# main_esp.net
KiCad netlist of a schematic drawn in Altium Designer
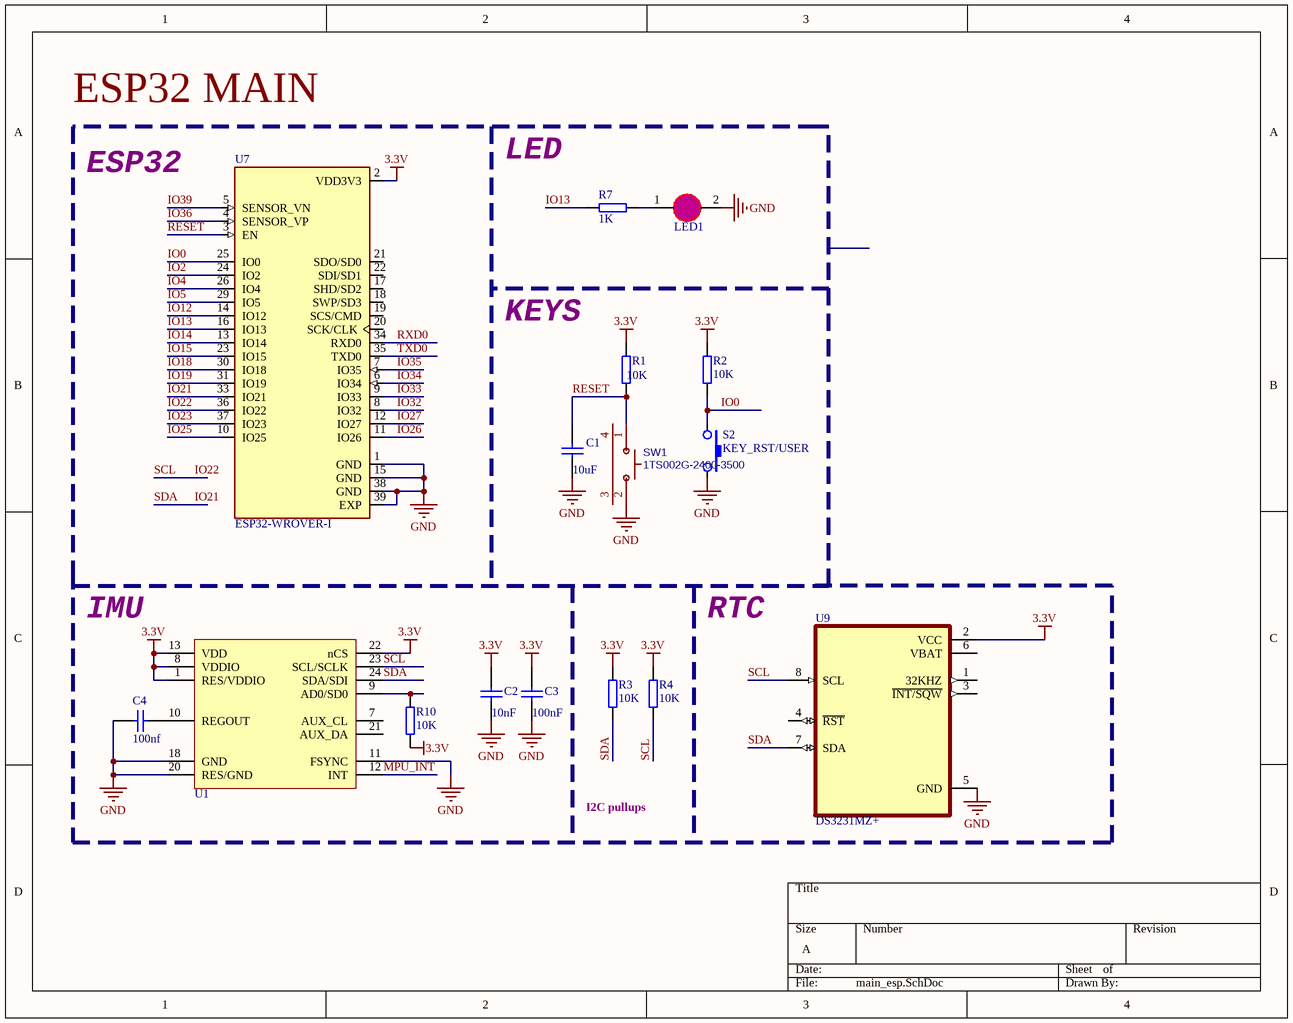
[diagram p0: main_esp.SchDoc]

(export (version "E")
  (design (tool "Eeschema 10.0.6"))
  (components
    (comp (ref "C1")
      (value "10uF")
      (footprint "SMT0603")
      (description "CAP SM 0603 X5R 10uF 10%")
      (fields (field (name "TOLERANCE") "±10%") (field (name "Comment") "Cap Semi"))
      (libsource (lib "electronpowered") (part "CAP-SM-0603-X5R-10uF"))
    )
    (comp (ref "C2")
      (value "10nF")
      (footprint "SMT0603")
      (description "CAP SM 0603 X5R 10uF 10%")
      (fields (field (name "TOLERANCE") "±10%") (field (name "Comment") "Cap Semi"))
      (libsource (lib "electronpowered") (part "CAP-SM-0603-X5R-10uF"))
    )
    (comp (ref "C3")
      (value "100nF")
      (footprint "SMT0603")
      (description "CAP SM 0603 X7R 100nF 10%")
      (fields (field (name "TOLERANCE") "±10%") (field (name "Comment") "Cap Semi"))
      (libsource (lib "electronpowered") (part "CAP-SM-0603-X7R-100nF"))
    )
    (comp (ref "C4")
      (value "100nf")
      (footprint "SMT0603")
      (description "CAP SM 0603 X5R 10uF 10%")
      (fields (field (name "TOLERANCE") "±10%") (field (name "Comment") "Cap Semi"))
      (libsource (lib "electronpowered") (part "CAP-SM-0603-X5R-10uF"))
    )
    (comp (ref "LED1")
      (value "LED3")
      (footprint "LED0805")
      (description "LED SMD 0805")
      (libsource (lib "My Library") (part "LED0805"))
    )
    (comp (ref "R1")
      (value "10K")
      (footprint "SMT0603")
      (description "RES SM 0603 10K")
      (fields (field (name "Comment") "Resistor"))
      (libsource (lib "electronpowered") (part "RES-SM-0603-10K"))
    )
    (comp (ref "R2")
      (value "10K")
      (footprint "SMT0603")
      (description "RES SM 0603 10K")
      (fields (field (name "Comment") "Resistor"))
      (libsource (lib "electronpowered") (part "RES-SM-0603-10K"))
    )
    (comp (ref "R3")
      (value "10K")
      (footprint "SMT0603")
      (description "RES SM 0603 10K")
      (fields (field (name "Comment") "Resistor"))
      (libsource (lib "electronpowered") (part "RES-SM-0603-10K"))
    )
    (comp (ref "R4")
      (value "10K")
      (footprint "SMT0603")
      (description "RES SM 0603 10K")
      (fields (field (name "Comment") "Resistor"))
      (libsource (lib "electronpowered") (part "RES-SM-0603-10K"))
    )
    (comp (ref "R7")
      (value "1K")
      (footprint "SMT0603")
      (description "RES SM 0603 1K")
      (fields (field (name "Comment") "Resistor"))
      (libsource (lib "electronpowered") (part "RES-SM-0603-1K"))
    )
    (comp (ref "R10")
      (value "10K")
      (footprint "SMT0603")
      (description "RES SM 0603 10K")
      (fields (field (name "Comment") "Resistor"))
      (libsource (lib "electronpowered") (part "RES-SM-0603-10K"))
    )
    (comp (ref "S2")
      (value "KEY_RST/USER")
      (footprint "SMT_SW_PTS_820")
      (description "SMT Tactile ‎Switch PTS 820 Series")
      (libsource (lib "NODEMCU_DEVKIT_V1.0") (part "SMT_SW_PTS_820"))
    )
    (comp (ref "SW1")
      (value "1TS002G-2400-3500")
      (footprint "KEY-SMD_1TS002G")
      (fields (field (name "BOM_SUPPLIER PART") "C319378") (field (name "CONTRIBUTOR") "LCSC"))
      (libsource (lib "SW") (part "1TS002G-2400-3500"))
    )
    (comp (ref "U1") (value "MPU-9250") (libsource (lib "MPU-9250") (part "MPU-9250")))
    (comp (ref "U7")
      (value "ESP32-WROVER-I")
      (footprint "SnapEDApcb:XCVR_ESP32-WROVER-I")
      (fields (field (name "MF") "Espressif Systems"))
      (libsource (lib "SnapEDAsch") (part "ESP32-WROVER-I"))
    )
    (comp (ref "U9")
      (value "DS3231MZ+")
      (footprint "SOIC127P600X175-8N")
      (description "Real Time Clock _RTC_ IC Clock/Calendar IÂ²C, 2-Wire Serial 8-SOIC _0.154, 3.90mm Width_")
      (fields (field (name "MP") "DS3231MZ") (field (name "MF") "Maxim Integrated"))
      (libsource (lib "DS3231MZ_") (part "DS3231MZ+"))
    )
  )
  (nets
    (net (code "1") (name "/IO0") (class "Default")
      (node (ref "R2") (pin "1") (pinfunction "1_1") (pintype "passive"))
      (node (ref "S2") (pin "1") (pinfunction "1_1") (pintype "passive"))
      (node (ref "U7") (pin "25") (pinfunction "IO0_25") (pintype "bidirectional"))
    )
    (net (code "2") (name "/IO2") (class "Default")
      (node (ref "U7") (pin "24") (pinfunction "IO2_24") (pintype "bidirectional"))
    )
    (net (code "3") (name "/IO4") (class "Default")
      (node (ref "U7") (pin "26") (pinfunction "IO4_26") (pintype "bidirectional"))
    )
    (net (code "4") (name "/IO5") (class "Default")
      (node (ref "U7") (pin "29") (pinfunction "IO5_29") (pintype "bidirectional"))
    )
    (net (code "5") (name "/IO12") (class "Default")
      (node (ref "U7") (pin "14") (pinfunction "IO12_14") (pintype "bidirectional"))
    )
    (net (code "6") (name "/IO13") (class "Default")
      (node (ref "R7") (pin "1") (pinfunction "1_1") (pintype "passive"))
      (node (ref "U7") (pin "16") (pinfunction "IO13_16") (pintype "bidirectional"))
    )
    (net (code "7") (name "/IO14") (class "Default")
      (node (ref "U7") (pin "13") (pinfunction "IO14_13") (pintype "bidirectional"))
    )
    (net (code "8") (name "/IO15") (class "Default")
      (node (ref "U7") (pin "23") (pinfunction "IO15_23") (pintype "bidirectional"))
    )
    (net (code "9") (name "/IO18") (class "Default")
      (node (ref "U7") (pin "30") (pinfunction "IO18_30") (pintype "bidirectional"))
    )
    (net (code "10") (name "/IO19") (class "Default")
      (node (ref "U7") (pin "31") (pinfunction "IO19_31") (pintype "bidirectional"))
    )
    (net (code "11") (name "/IO21") (class "Default")
      (node (ref "R3") (pin "1") (pinfunction "1_1") (pintype "passive"))
      (node (ref "U1") (pin "24") (pinfunction "SDA/SDI_24") (pintype "passive"))
      (node (ref "U7") (pin "33") (pinfunction "IO21_33") (pintype "bidirectional"))
      (node (ref "U9") (pin "7") (pinfunction "SDA_7") (pintype "bidirectional"))
    )
    (net (code "12") (name "/IO22") (class "Default")
      (node (ref "R4") (pin "1") (pinfunction "1_1") (pintype "passive"))
      (node (ref "U1") (pin "23") (pinfunction "SCL/SCLK_23") (pintype "passive"))
      (node (ref "U7") (pin "36") (pinfunction "IO22_36") (pintype "bidirectional"))
      (node (ref "U9") (pin "8") (pinfunction "SCL_8") (pintype "input"))
    )
    (net (code "13") (name "/IO23") (class "Default")
      (node (ref "U7") (pin "37") (pinfunction "IO23_37") (pintype "bidirectional"))
    )
    (net (code "14") (name "/IO25") (class "Default")
      (node (ref "U7") (pin "10") (pinfunction "IO25_10") (pintype "bidirectional"))
    )
    (net (code "15") (name "/IO26") (class "Default")
      (node (ref "U7") (pin "11") (pinfunction "IO26_11") (pintype "bidirectional"))
    )
    (net (code "16") (name "/IO27") (class "Default")
      (node (ref "U7") (pin "12") (pinfunction "IO27_12") (pintype "bidirectional"))
    )
    (net (code "17") (name "/IO32") (class "Default")
      (node (ref "U7") (pin "8") (pinfunction "IO32_8") (pintype "bidirectional"))
    )
    (net (code "18") (name "/IO33") (class "Default")
      (node (ref "U7") (pin "9") (pinfunction "IO33_9") (pintype "bidirectional"))
    )
    (net (code "19") (name "/IO34") (class "Default")
      (node (ref "U7") (pin "6") (pinfunction "IO34_6") (pintype "input"))
    )
    (net (code "20") (name "/IO35") (class "Default")
      (node (ref "U7") (pin "7") (pinfunction "IO35_7") (pintype "input"))
    )
    (net (code "21") (name "/IO36") (class "Default")
      (node (ref "U7") (pin "4") (pinfunction "SENSOR_VP_4") (pintype "input"))
    )
    (net (code "22") (name "/IO39") (class "Default")
      (node (ref "U7") (pin "5") (pinfunction "SENSOR_VN_5") (pintype "input"))
    )
    (net (code "23") (name "/MPU_INT") (class "Default")
      (node (ref "U1") (pin "12") (pinfunction "INT_12") (pintype "passive"))
    )
    (net (code "24") (name "/RESET") (class "Default")
      (node (ref "C1") (pin "2") (pinfunction "2_2") (pintype "passive"))
      (node (ref "R1") (pin "1") (pinfunction "1_1") (pintype "passive"))
      (node (ref "SW1") (pin "1") (pinfunction "1_1") (pintype "passive"))
      (node (ref "U7") (pin "3") (pinfunction "EN_3") (pintype "input"))
    )
    (net (code "25") (name "/RXD0") (class "Default")
      (node (ref "U7") (pin "34") (pinfunction "RXD0_34") (pintype "bidirectional"))
    )
    (net (code "26") (name "/TXD0") (class "Default")
      (node (ref "U7") (pin "35") (pinfunction "TXD0_35") (pintype "bidirectional"))
    )
    (net (code "27") (name "3.3V") (class "Default")
      (node (ref "C2") (pin "2") (pinfunction "2_2") (pintype "passive"))
      (node (ref "C3") (pin "2") (pinfunction "2_2") (pintype "passive"))
      (node (ref "R1") (pin "2") (pinfunction "2_2") (pintype "passive"))
      (node (ref "R10") (pin "1") (pinfunction "1_1") (pintype "passive"))
      (node (ref "R2") (pin "2") (pinfunction "2_2") (pintype "passive"))
      (node (ref "R3") (pin "2") (pinfunction "2_2") (pintype "passive"))
      (node (ref "R4") (pin "2") (pinfunction "2_2") (pintype "passive"))
      (node (ref "U1") (pin "1") (pinfunction "RES/VDDIO_1") (pintype "passive"))
      (node (ref "U1") (pin "13") (pinfunction "VDD_13") (pintype "passive"))
      (node (ref "U1") (pin "22") (pinfunction "nCS_22") (pintype "passive"))
      (node (ref "U1") (pin "8") (pinfunction "VDDIO_8") (pintype "passive"))
      (node (ref "U7") (pin "2") (pinfunction "VDD3V3_2") (pintype "power_in"))
      (node (ref "U9") (pin "2") (pinfunction "VCC_2") (pintype "power_in"))
    )
    (net (code "28") (name "GND") (class "Default")
      (node (ref "C1") (pin "1") (pinfunction "1_1") (pintype "passive"))
      (node (ref "C2") (pin "1") (pinfunction "1_1") (pintype "passive"))
      (node (ref "C3") (pin "1") (pinfunction "1_1") (pintype "passive"))
      (node (ref "C4") (pin "2") (pinfunction "2_2") (pintype "passive"))
      (node (ref "LED1") (pin "2") (pinfunction "K_2") (pintype "passive"))
      (node (ref "S2") (pin "2") (pinfunction "2_2") (pintype "passive"))
      (node (ref "SW1") (pin "2") (pinfunction "2_2") (pintype "passive"))
      (node (ref "U1") (pin "11") (pinfunction "FSYNC_11") (pintype "passive"))
      (node (ref "U1") (pin "18") (pinfunction "GND_18") (pintype "passive"))
      (node (ref "U1") (pin "20") (pinfunction "RES/GND_20") (pintype "passive"))
      (node (ref "U7") (pin "1") (pinfunction "GND_1") (pintype "power_in"))
      (node (ref "U7") (pin "15") (pinfunction "GND_15") (pintype "power_in"))
      (node (ref "U7") (pin "38") (pinfunction "GND_38") (pintype "power_in"))
      (node (ref "U7") (pin "39") (pinfunction "EXP_39") (pintype "power_in"))
      (node (ref "U9") (pin "5") (pinfunction "GND_5") (pintype "power_in"))
    )
    (net (code "29") (name "Net-(LED1-A)") (class "Default")
      (node (ref "LED1") (pin "1") (pinfunction "A_1") (pintype "passive"))
      (node (ref "R7") (pin "2") (pinfunction "2_2") (pintype "passive"))
    )
    (net (code "30") (name "Net-(U1-AD0{slash}SD0)") (class "Default")
      (node (ref "R10") (pin "2") (pinfunction "2_2") (pintype "passive"))
      (node (ref "U1") (pin "9") (pinfunction "AD0/SD0_9") (pintype "passive"))
    )
    (net (code "31") (name "Net-(U1-REGOUT)") (class "Default")
      (node (ref "C4") (pin "1") (pinfunction "1_1") (pintype "passive"))
      (node (ref "U1") (pin "10") (pinfunction "REGOUT_10") (pintype "passive"))
    )
    (net (code "32") (name "unconnected-(SW1-Pad3)") (class "Default")
      (node (ref "SW1") (pin "3") (pinfunction "3_3") (pintype "passive"))
    )
    (net (code "33") (name "unconnected-(SW1-Pad4)") (class "Default")
      (node (ref "SW1") (pin "4") (pinfunction "4_4") (pintype "passive"))
    )
    (net (code "34") (name "unconnected-(U1-AUX_CL-Pad7)") (class "Default")
      (node (ref "U1") (pin "7") (pinfunction "AUX_CL_7") (pintype "passive"))
    )
    (net (code "35") (name "unconnected-(U1-AUX_DA-Pad21)") (class "Default")
      (node (ref "U1") (pin "21") (pinfunction "AUX_DA_21") (pintype "passive"))
    )
    (net (code "36") (name "unconnected-(U7-SCK{slash}CLK-Pad20)") (class "Default")
      (node (ref "U7") (pin "20") (pinfunction "SCK/CLK_20") (pintype "bidirectional"))
    )
    (net (code "37") (name "unconnected-(U7-SCS{slash}CMD-Pad19)") (class "Default")
      (node (ref "U7") (pin "19") (pinfunction "SCS/CMD_19") (pintype "bidirectional"))
    )
    (net (code "38") (name "unconnected-(U7-SDI{slash}SD1-Pad22)") (class "Default")
      (node (ref "U7") (pin "22") (pinfunction "SDI/SD1_22") (pintype "bidirectional"))
    )
    (net (code "39") (name "unconnected-(U7-SDO{slash}SD0-Pad21)") (class "Default")
      (node (ref "U7") (pin "21") (pinfunction "SDO/SD0_21") (pintype "bidirectional"))
    )
    (net (code "40") (name "unconnected-(U7-SHD{slash}SD2-Pad17)") (class "Default")
      (node (ref "U7") (pin "17") (pinfunction "SHD/SD2_17") (pintype "bidirectional"))
    )
    (net (code "41") (name "unconnected-(U7-SWP{slash}SD3-Pad18)") (class "Default")
      (node (ref "U7") (pin "18") (pinfunction "SWP/SD3_18") (pintype "bidirectional"))
    )
    (net (code "42") (name "unconnected-(U9-32KHZ-Pad1)") (class "Default")
      (node (ref "U9") (pin "1") (pinfunction "32KHZ_1") (pintype "output"))
    )
    (net (code "43") (name "unconnected-(U9-VBAT-Pad6)") (class "Default")
      (node (ref "U9") (pin "6") (pinfunction "VBAT_6") (pintype "power_in"))
    )
    (net (code "44") (name "unconnected-(U9-~{INT{slash}SQW}-Pad3)") (class "Default")
      (node (ref "U9") (pin "3") (pinfunction "~{INT/SQW}_3") (pintype "output"))
    )
    (net (code "45") (name "unconnected-(U9-~{RST}-Pad4)") (class "Default")
      (node (ref "U9") (pin "4") (pinfunction "~{RST}_4") (pintype "bidirectional"))
    )
  )
)
